# GRLV_double_30v_v0_2b.net
KiCad netlist of a schematic drawn in Altium Designer
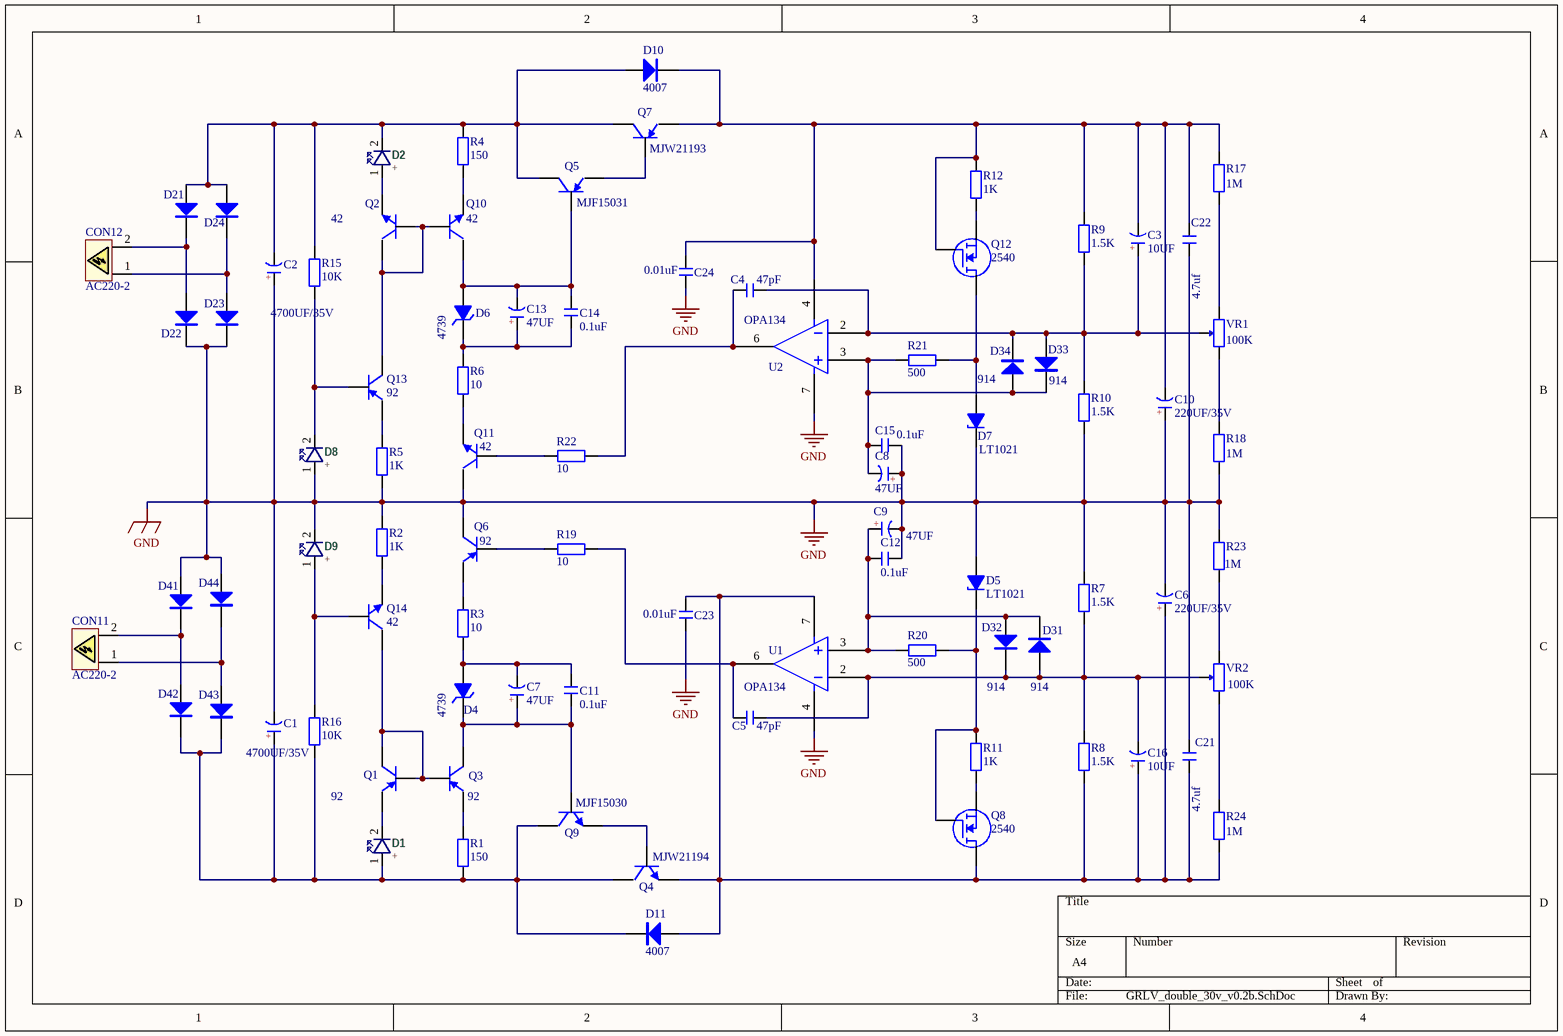
[diagram p0: GRLV_double_30v_v0.2b.SchDoc]

(export (version "E")
  (design (tool "Eeschema 10.0.6"))
  (components
    (comp (ref "C1")
      (value "4700UF/35V")
      (footprint "CAP 10*22*31.5")
      (description "直插电解电容")
      (fields (field (name "版权归属") "源创客"))
      (libsource (lib "电阻-电容-电感") (part "C-CAP"))
    )
    (comp (ref "C2")
      (value "4700UF/35V")
      (footprint "CAP 10*22*31.5")
      (description "直插电解电容")
      (fields (field (name "版权归属") "源创客"))
      (libsource (lib "电阻-电容-电感") (part "C-CAP"))
    )
    (comp (ref "C3")
      (value "10UF")
      (footprint "CAP 2.5*6.3*7")
      (description "直插电解电容")
      (fields (field (name "版权归属") "源创客"))
      (libsource (lib "电阻-电容-电感") (part "C-CAP"))
    )
    (comp (ref "C4")
      (value "47pF")
      (footprint "CBB 6.3*6.3*5")
      (description "CBB电容")
      (fields (field (name "版权归属") "源创客"))
      (libsource (lib "电阻-电容-电感") (part "C-CBB"))
    )
    (comp (ref "C5")
      (value "47pF")
      (footprint "CBB 6.3*6.3*5")
      (description "CBB电容")
      (fields (field (name "版权归属") "源创客"))
      (libsource (lib "电阻-电容-电感") (part "C-CBB"))
    )
    (comp (ref "C6")
      (value "220UF/35V")
      (footprint "CAP 3.5*8*11.5")
      (description "直插电解电容")
      (fields (field (name "版权归属") "源创客"))
      (libsource (lib "电阻-电容-电感") (part "C-CAP"))
    )
    (comp (ref "C7")
      (value "47UF")
      (footprint "CAP 2.5*6.3*11.2")
      (description "直插电解电容")
      (fields (field (name "版权归属") "源创客"))
      (libsource (lib "电阻-电容-电感") (part "C-CAP"))
    )
    (comp (ref "C8")
      (value "47UF")
      (footprint "CAP 2.5*6.3*11.2")
      (description "直插电解电容")
      (fields (field (name "版权归属") "源创客"))
      (libsource (lib "") (part "C-CAP_1"))
    )
    (comp (ref "C9")
      (value "47UF")
      (footprint "CAP 2.5*6.3*11.2")
      (description "直插电解电容")
      (fields (field (name "版权归属") "源创客"))
      (libsource (lib "") (part "C-CAP_1"))
    )
    (comp (ref "C10")
      (value "220UF/35V")
      (footprint "CAP 3.5*8*11.5")
      (description "直插电解电容")
      (fields (field (name "版权归属") "源创客"))
      (libsource (lib "电阻-电容-电感") (part "C-CAP"))
    )
    (comp (ref "C11")
      (value "0.1uF")
      (footprint "CBB 6.3*6.3*5")
      (description "CBB电容")
      (fields (field (name "版权归属") "源创客"))
      (libsource (lib "电阻-电容-电感") (part "C-CBB"))
    )
    (comp (ref "C12")
      (value "0.1uF")
      (footprint "CBB 6.3*6.3*5")
      (description "CBB电容")
      (fields (field (name "版权归属") "源创客"))
      (libsource (lib "电阻-电容-电感") (part "C-CBB"))
    )
    (comp (ref "C13")
      (value "47UF")
      (footprint "CAP 2.5*6.3*11.2")
      (description "直插电解电容")
      (fields (field (name "版权归属") "源创客"))
      (libsource (lib "电阻-电容-电感") (part "C-CAP"))
    )
    (comp (ref "C14")
      (value "0.1uF")
      (footprint "CBB 6.3*6.3*5")
      (description "CBB电容")
      (fields (field (name "版权归属") "源创客"))
      (libsource (lib "电阻-电容-电感") (part "C-CBB"))
    )
    (comp (ref "C15")
      (value "0.1uF")
      (footprint "CBB 6.3*6.3*5")
      (description "CBB电容")
      (fields (field (name "版权归属") "源创客"))
      (libsource (lib "电阻-电容-电感") (part "C-CBB"))
    )
    (comp (ref "C16")
      (value "10UF")
      (footprint "CAP 2.5*6.3*7")
      (description "直插电解电容")
      (fields (field (name "版权归属") "源创客"))
      (libsource (lib "电阻-电容-电感") (part "C-CAP"))
    )
    (comp (ref "C21")
      (value "4.7uf")
      (footprint "CBB 7.2*7.2*13")
      (description "MKS薄膜电容")
      (libsource (lib "电阻-电容-电感") (part "C-MKS"))
    )
    (comp (ref "C22")
      (value "4.7uf")
      (footprint "CBB 7.2*7.2*13")
      (description "MKS薄膜电容")
      (libsource (lib "电阻-电容-电感") (part "C-MKS"))
    )
    (comp (ref "C23")
      (value "0.01uF")
      (footprint "CBB 6.3*6.3*5")
      (description "CBB电容")
      (fields (field (name "Comment") ".01") (field (name "版权归属") "源创客"))
      (libsource (lib "电阻-电容-电感") (part "C-CBB"))
    )
    (comp (ref "C24")
      (value "0.01uF")
      (footprint "CBB 6.3*6.3*5")
      (description "CBB电容")
      (fields (field (name "Comment") ".01") (field (name "版权归属") "源创客"))
      (libsource (lib "电阻-电容-电感") (part "C-CBB"))
    )
    (comp (ref "CON11")
      (value "AC220-2")
      (footprint "HX4.0-2XS")
      (libsource (lib "Connectors") (part "AC220-2"))
    )
    (comp (ref "CON12")
      (value "AC220-2")
      (footprint "HX4.0-2XS")
      (libsource (lib "Connectors") (part "AC220-2"))
    )
    (comp (ref "D1")
      (value "+")
      (footprint "LED 3MM-R")
      (description "直插式LED")
      (libsource (lib "LED") (part "LED"))
    )
    (comp (ref "D2")
      (value "+")
      (footprint "LED 3MM-R")
      (description "直插式LED")
      (libsource (lib "LED") (part "LED"))
    )
    (comp (ref "D4")
      (value "4739")
      (footprint "DO-41")
      (description "9.1V/1W稳压管")
      (libsource (lib "二极管-整流桥") (part "1N4739"))
    )
    (comp (ref "D5")
      (value "LT1021")
      (footprint "DIP8-300_MH")
      (description "10V Precision Reference 2 Pin Config")
      (libsource (lib "电压参考") (part "LT1021-10-2P"))
    )
    (comp (ref "D6")
      (value "4739")
      (footprint "DO-41")
      (description "9.1V/1W稳压管")
      (libsource (lib "二极管-整流桥") (part "1N4739"))
    )
    (comp (ref "D7")
      (value "LT1021")
      (footprint "DIP8-300_MH")
      (description "10V Precision Reference 2 Pin Config")
      (libsource (lib "电压参考") (part "LT1021-10-2P"))
    )
    (comp (ref "D8")
      (value "+")
      (footprint "LED 3MM-R")
      (description "直插式LED")
      (libsource (lib "LED") (part "LED"))
    )
    (comp (ref "D9")
      (value "+")
      (footprint "LED 3MM-R")
      (description "直插式LED")
      (libsource (lib "LED") (part "LED"))
    )
    (comp (ref "D10")
      (value "4007")
      (footprint "DO-41")
      (description "整流二极管")
      (fields (field (name "版权归属") "源创客"))
      (libsource (lib "二极管-整流桥") (part "1N4007"))
    )
    (comp (ref "D11")
      (value "4007")
      (footprint "DO-41")
      (description "整流二极管")
      (fields (field (name "版权归属") "源创客"))
      (libsource (lib "二极管-整流桥") (part "1N4007"))
    )
    (comp (ref "D21")
      (value "HFA08")
      (footprint "TO220AC")
      (description "Ultrafast Soft Recovery Diado 8A 600V")
      (libsource (lib "二极管-整流桥") (part "VS-HFA08TB60-M3"))
    )
    (comp (ref "D22")
      (value "HFA08")
      (footprint "TO220AC")
      (description "Ultrafast Soft Recovery Diado 8A 600V")
      (libsource (lib "二极管-整流桥") (part "VS-HFA08TB60-M3"))
    )
    (comp (ref "D23")
      (value "HFA08")
      (footprint "TO220AC")
      (description "Ultrafast Soft Recovery Diado 8A 600V")
      (libsource (lib "二极管-整流桥") (part "VS-HFA08TB60-M3"))
    )
    (comp (ref "D24")
      (value "HFA08")
      (footprint "TO220AC")
      (description "Ultrafast Soft Recovery Diado 8A 600V")
      (libsource (lib "二极管-整流桥") (part "VS-HFA08TB60-M3"))
    )
    (comp (ref "D31")
      (value "914")
      (footprint "DO-35")
      (description "高速开关管 1V/0.25W")
      (libsource (lib "二极管-整流桥") (part "1N914"))
    )
    (comp (ref "D32")
      (value "914")
      (footprint "DO-35")
      (description "高速开关管 1V/0.25W")
      (libsource (lib "二极管-整流桥") (part "1N914"))
    )
    (comp (ref "D33")
      (value "914")
      (footprint "DO-35")
      (description "高速开关管 1V/0.25W")
      (libsource (lib "二极管-整流桥") (part "1N914"))
    )
    (comp (ref "D34")
      (value "914")
      (footprint "DO-35")
      (description "高速开关管 1V/0.25W")
      (libsource (lib "二极管-整流桥") (part "1N914"))
    )
    (comp (ref "D41")
      (value "VS-HFA08TB60-M3")
      (footprint "TO220AC")
      (description "Ultrafast Soft Recovery Diado 8A 600V")
      (libsource (lib "二极管-整流桥") (part "VS-HFA08TB60-M3"))
    )
    (comp (ref "D42")
      (value "VS-HFA08TB60-M3")
      (footprint "TO220AC")
      (description "Ultrafast Soft Recovery Diado 8A 600V")
      (libsource (lib "二极管-整流桥") (part "VS-HFA08TB60-M3"))
    )
    (comp (ref "D43")
      (value "VS-HFA08TB60-M3")
      (footprint "TO220AC")
      (description "Ultrafast Soft Recovery Diado 8A 600V")
      (libsource (lib "二极管-整流桥") (part "VS-HFA08TB60-M3"))
    )
    (comp (ref "D44")
      (value "VS-HFA08TB60-M3")
      (footprint "TO220AC")
      (description "Ultrafast Soft Recovery Diado 8A 600V")
      (libsource (lib "二极管-整流桥") (part "VS-HFA08TB60-M3"))
    )
    (comp (ref "Q1")
      (value "92")
      (footprint "TO92A")
      (description "High Voltage PNP Transistor")
      (libsource (lib "三极管") (part "KSP92/93"))
    )
    (comp (ref "Q2")
      (value "42")
      (footprint "TO92A")
      (description "High Voltage NPN Transistor")
      (libsource (lib "三极管") (part "KSP42/43"))
    )
    (comp (ref "Q3")
      (value "92")
      (footprint "TO92A")
      (description "High Voltage PNP Transistor")
      (libsource (lib "三极管") (part "KSP92/93"))
    )
    (comp (ref "Q4")
      (value "MJW21194")
      (footprint "TO247V")
      (description "Power NPN Transistor")
      (libsource (lib "三极管") (part "MJW21194"))
    )
    (comp (ref "Q5")
      (value "MJF15031")
      (footprint "TO220V")
      (description "Power PNP Transistor")
      (libsource (lib "三极管") (part "MJF15031"))
    )
    (comp (ref "Q6")
      (value "92")
      (footprint "TO92A")
      (description "High Voltage PNP Transistor")
      (libsource (lib "三极管") (part "KSP92/93"))
    )
    (comp (ref "Q7")
      (value "MJW21193")
      (footprint "TO247V")
      (description "Power PNP Transistor")
      (libsource (lib "三极管") (part "MJW21193"))
    )
    (comp (ref "Q8")
      (value "2540")
      (footprint "TO92A")
      (description "N沟道耗尽型DMOS场效应管 400V/150ma")
      (libsource (lib "场效应管") (part "DN2540"))
    )
    (comp (ref "Q9")
      (value "MJF15030")
      (footprint "TO220V")
      (description "Power NPN Transistor")
      (libsource (lib "三极管") (part "MJF15030"))
    )
    (comp (ref "Q10")
      (value "42")
      (footprint "TO92A")
      (description "High Voltage NPN Transistor")
      (libsource (lib "三极管") (part "KSP42/43"))
    )
    (comp (ref "Q11")
      (value "42")
      (footprint "TO92A")
      (description "High Voltage NPN Transistor")
      (libsource (lib "三极管") (part "KSP42/43"))
    )
    (comp (ref "Q12")
      (value "2540")
      (footprint "TO92A")
      (description "N沟道耗尽型DMOS场效应管 400V/150ma")
      (libsource (lib "场效应管") (part "DN2540"))
    )
    (comp (ref "Q13")
      (value "92")
      (footprint "TO92A")
      (description "High Voltage PNP Transistor")
      (libsource (lib "三极管") (part "KSP92/93"))
    )
    (comp (ref "Q14")
      (value "42")
      (footprint "TO92A")
      (description "High Voltage NPN Transistor")
      (libsource (lib "三极管") (part "KSP42/43"))
    )
    (comp (ref "R1")
      (value "150")
      (footprint "RS 1/4W")
      (description "直插色环电阻")
      (fields (field (name "版权归属") "源创客"))
      (libsource (lib "电阻-电容-电感") (part "R-CRR"))
    )
    (comp (ref "R2")
      (value "1K")
      (footprint "RS 1/4W")
      (description "直插色环电阻")
      (fields (field (name "版权归属") "源创客"))
      (libsource (lib "电阻-电容-电感") (part "R-CRR"))
    )
    (comp (ref "R3")
      (value "10")
      (footprint "RS 1/4W")
      (description "直插色环电阻")
      (fields (field (name "版权归属") "源创客"))
      (libsource (lib "电阻-电容-电感") (part "R-CRR"))
    )
    (comp (ref "R4")
      (value "150")
      (footprint "RS 1/4W")
      (description "直插色环电阻")
      (fields (field (name "版权归属") "源创客"))
      (libsource (lib "电阻-电容-电感") (part "R-CRR"))
    )
    (comp (ref "R5")
      (value "1K")
      (footprint "RS 1/4W")
      (description "直插色环电阻")
      (fields (field (name "版权归属") "源创客"))
      (libsource (lib "电阻-电容-电感") (part "R-CRR"))
    )
    (comp (ref "R6")
      (value "10")
      (footprint "RS 1/4W")
      (description "直插色环电阻")
      (fields (field (name "版权归属") "源创客"))
      (libsource (lib "电阻-电容-电感") (part "R-CRR"))
    )
    (comp (ref "R7")
      (value "1.5K")
      (footprint "RS 1/4W")
      (description "直插色环电阻")
      (fields (field (name "版权归属") "源创客"))
      (libsource (lib "电阻-电容-电感") (part "R-CRR"))
    )
    (comp (ref "R8")
      (value "1.5K")
      (footprint "RS 1/4W")
      (description "直插色环电阻")
      (fields (field (name "版权归属") "源创客"))
      (libsource (lib "电阻-电容-电感") (part "R-CRR"))
    )
    (comp (ref "R9")
      (value "1.5K")
      (footprint "RS 1/4W")
      (description "直插色环电阻")
      (fields (field (name "版权归属") "源创客"))
      (libsource (lib "电阻-电容-电感") (part "R-CRR"))
    )
    (comp (ref "R10")
      (value "1.5K")
      (footprint "RS 1/4W")
      (description "直插色环电阻")
      (fields (field (name "版权归属") "源创客"))
      (libsource (lib "电阻-电容-电感") (part "R-CRR"))
    )
    (comp (ref "R11")
      (value "1K")
      (footprint "RS 1/4W")
      (description "直插色环电阻")
      (fields (field (name "版权归属") "源创客"))
      (libsource (lib "电阻-电容-电感") (part "R-CRR"))
    )
    (comp (ref "R12")
      (value "1K")
      (footprint "RS 1/4W")
      (description "直插色环电阻")
      (fields (field (name "版权归属") "源创客"))
      (libsource (lib "电阻-电容-电感") (part "R-CRR"))
    )
    (comp (ref "R15")
      (value "10K")
      (footprint "RS 1/4W")
      (description "直插色环电阻")
      (fields (field (name "版权归属") "源创客"))
      (libsource (lib "电阻-电容-电感") (part "R-CRR"))
    )
    (comp (ref "R16")
      (value "10K")
      (footprint "RS 1/4W")
      (description "直插色环电阻")
      (fields (field (name "版权归属") "源创客"))
      (libsource (lib "电阻-电容-电感") (part "R-CRR"))
    )
    (comp (ref "R17")
      (value "1M")
      (footprint "RS 1/4W")
      (description "直插色环电阻")
      (fields (field (name "版权归属") "源创客"))
      (libsource (lib "电阻-电容-电感") (part "R-CRR"))
    )
    (comp (ref "R18")
      (value "1M")
      (footprint "RS 1/4W")
      (description "直插色环电阻")
      (fields (field (name "版权归属") "源创客"))
      (libsource (lib "电阻-电容-电感") (part "R-CRR"))
    )
    (comp (ref "R19")
      (value "10")
      (footprint "RS 1/4W")
      (description "直插色环电阻")
      (fields (field (name "版权归属") "源创客"))
      (libsource (lib "电阻-电容-电感") (part "R-CRR"))
    )
    (comp (ref "R20")
      (value "500")
      (footprint "RS 1/4W")
      (description "直插色环电阻")
      (fields (field (name "版权归属") "源创客"))
      (libsource (lib "电阻-电容-电感") (part "R-CRR"))
    )
    (comp (ref "R21")
      (value "500")
      (footprint "RS 1/4W")
      (description "直插色环电阻")
      (fields (field (name "版权归属") "源创客"))
      (libsource (lib "电阻-电容-电感") (part "R-CRR"))
    )
    (comp (ref "R22")
      (value "10")
      (footprint "RS 1/4W")
      (description "直插色环电阻")
      (fields (field (name "版权归属") "源创客"))
      (libsource (lib "电阻-电容-电感") (part "R-CRR"))
    )
    (comp (ref "R23")
      (value "1M")
      (footprint "RS 1/4W")
      (description "直插色环电阻")
      (fields (field (name "版权归属") "源创客"))
      (libsource (lib "电阻-电容-电感") (part "R-CRR"))
    )
    (comp (ref "R24")
      (value "1M")
      (footprint "RS 1/4W")
      (description "直插色环电阻")
      (fields (field (name "版权归属") "源创客"))
      (libsource (lib "电阻-电容-电感") (part "R-CRR"))
    )
    (comp (ref "U1") (value "OPA134") (footprint "DIP8-300_MH") (libsource (lib "运放") (part "OPA134PA")))
    (comp (ref "U2") (value "OPA134") (footprint "DIP8-300_MH") (libsource (lib "运放") (part "OPA134PA")))
    (comp (ref "VR1")
      (value "100K")
      (footprint "RS 1/2W-VR")
      (description "直插可调电阻-顶调")
      (libsource (lib "电阻-电容-电感") (part "VR-W"))
    )
    (comp (ref "VR2")
      (value "100K")
      (footprint "RS 1/2W-VR")
      (description "直插可调电阻-顶调")
      (libsource (lib "电阻-电容-电感") (part "VR-W"))
    )
  )
  (nets
    (net (code "1") (name "GND") (class "Default")
      (node (ref "C1") (pin "2") (pinfunction "K_2") (pintype "passive"))
      (node (ref "C10") (pin "1") (pinfunction "A_1") (pintype "passive"))
      (node (ref "C12") (pin "2") (pinfunction "2_2") (pintype "passive"))
      (node (ref "C15") (pin "2") (pinfunction "2_2") (pintype "passive"))
      (node (ref "C2") (pin "1") (pinfunction "A_1") (pintype "passive"))
      (node (ref "C21") (pin "2") (pinfunction "2_2") (pintype "passive"))
      (node (ref "C22") (pin "1") (pinfunction "1_1") (pintype "passive"))
      (node (ref "C23") (pin "1") (pinfunction "1_1") (pintype "passive"))
      (node (ref "C24") (pin "1") (pinfunction "1_1") (pintype "passive"))
      (node (ref "C6") (pin "2") (pinfunction "K_2") (pintype "passive"))
      (node (ref "C8") (pin "1") (pinfunction "A_1") (pintype "passive"))
      (node (ref "C9") (pin "2") (pinfunction "K_2") (pintype "passive"))
      (node (ref "D22") (pin "1") (pinfunction "Cathode_1") (pintype "passive"))
      (node (ref "D23") (pin "1") (pinfunction "Cathode_1") (pintype "passive"))
      (node (ref "D41") (pin "2") (pinfunction "Anode_2") (pintype "passive"))
      (node (ref "D44") (pin "2") (pinfunction "Anode_2") (pintype "passive"))
      (node (ref "D5") (pin "4") (pinfunction "A_4") (pintype "passive"))
      (node (ref "D7") (pin "6") (pinfunction "K_6") (pintype "passive"))
      (node (ref "D8") (pin "1") (pinfunction "A_1") (pintype "passive"))
      (node (ref "D9") (pin "2") (pinfunction "K_2") (pintype "passive"))
      (node (ref "Q11") (pin "3") (pinfunction "C_3") (pintype "passive"))
      (node (ref "Q6") (pin "3") (pinfunction "C_3") (pintype "passive"))
      (node (ref "R10") (pin "1") (pinfunction "1_1") (pintype "passive"))
      (node (ref "R18") (pin "1") (pinfunction "1_1") (pintype "passive"))
      (node (ref "R2") (pin "2") (pinfunction "2_2") (pintype "passive"))
      (node (ref "R23") (pin "2") (pinfunction "2_2") (pintype "passive"))
      (node (ref "R5") (pin "1") (pinfunction "1_1") (pintype "passive"))
      (node (ref "R7") (pin "2") (pinfunction "2_2") (pintype "passive"))
      (node (ref "U1") (pin "4") (pinfunction "V-_4") (pintype "passive"))
      (node (ref "U2") (pin "7") (pinfunction "V+_7") (pintype "passive"))
    )
    (net (code "2") (name "Net-(C1-A)") (class "Default")
      (node (ref "C1") (pin "1") (pinfunction "A_1") (pintype "passive"))
      (node (ref "D1") (pin "1") (pinfunction "A_1") (pintype "passive"))
      (node (ref "D11") (pin "2") (pinfunction "K_2") (pintype "passive"))
      (node (ref "D42") (pin "1") (pinfunction "Cathode_1") (pintype "passive"))
      (node (ref "D43") (pin "1") (pinfunction "Cathode_1") (pintype "passive"))
      (node (ref "Q4") (pin "2") (pinfunction "C_2") (pintype "passive"))
      (node (ref "Q9") (pin "2") (pinfunction "C_2") (pintype "passive"))
      (node (ref "R1") (pin "1") (pinfunction "1_1") (pintype "passive"))
      (node (ref "R16") (pin "1") (pinfunction "1_1") (pintype "passive"))
    )
    (net (code "3") (name "Net-(C2-K)") (class "Default")
      (node (ref "C2") (pin "2") (pinfunction "K_2") (pintype "passive"))
      (node (ref "D10") (pin "1") (pinfunction "A_1") (pintype "passive"))
      (node (ref "D2") (pin "2") (pinfunction "K_2") (pintype "passive"))
      (node (ref "D21") (pin "2") (pinfunction "Anode_2") (pintype "passive"))
      (node (ref "D24") (pin "2") (pinfunction "Anode_2") (pintype "passive"))
      (node (ref "Q5") (pin "2") (pinfunction "C_2") (pintype "passive"))
      (node (ref "Q7") (pin "2") (pinfunction "C_2") (pintype "passive"))
      (node (ref "R15") (pin "2") (pinfunction "2_2") (pintype "passive"))
      (node (ref "R4") (pin "2") (pinfunction "2_2") (pintype "passive"))
    )
    (net (code "4") (name "Net-(C3-A)") (class "Default")
      (node (ref "C3") (pin "1") (pinfunction "A_1") (pintype "passive"))
      (node (ref "C4") (pin "2") (pinfunction "2_2") (pintype "passive"))
      (node (ref "D33") (pin "1") (pinfunction "A_1") (pintype "passive"))
      (node (ref "D34") (pin "2") (pinfunction "K_2") (pintype "passive"))
      (node (ref "R10") (pin "2") (pinfunction "2_2") (pintype "passive"))
      (node (ref "R9") (pin "1") (pinfunction "1_1") (pintype "passive"))
      (node (ref "U2") (pin "2") (pinfunction "-in_2") (pintype "passive"))
      (node (ref "VR1") (pin "3") (pinfunction "3_3") (pintype "passive"))
    )
    (net (code "5") (name "Net-(C7-A)") (class "Default")
      (node (ref "C11") (pin "1") (pinfunction "1_1") (pintype "passive"))
      (node (ref "C7") (pin "1") (pinfunction "A_1") (pintype "passive"))
      (node (ref "D4") (pin "2") (pinfunction "K_2") (pintype "passive"))
      (node (ref "Q3") (pin "3") (pinfunction "C_3") (pintype "passive"))
      (node (ref "Q9") (pin "1") (pinfunction "B_1") (pintype "passive"))
    )
    (net (code "6") (name "Net-(C7-K)") (class "Default")
      (node (ref "C11") (pin "2") (pinfunction "2_2") (pintype "passive"))
      (node (ref "C7") (pin "2") (pinfunction "K_2") (pintype "passive"))
      (node (ref "D4") (pin "1") (pinfunction "A_1") (pintype "passive"))
      (node (ref "R3") (pin "1") (pinfunction "1_1") (pintype "passive"))
    )
    (net (code "7") (name "Net-(C8-K)") (class "Default")
      (node (ref "C15") (pin "1") (pinfunction "1_1") (pintype "passive"))
      (node (ref "C8") (pin "2") (pinfunction "K_2") (pintype "passive"))
      (node (ref "D33") (pin "2") (pinfunction "K_2") (pintype "passive"))
      (node (ref "D34") (pin "1") (pinfunction "A_1") (pintype "passive"))
      (node (ref "R21") (pin "1") (pinfunction "1_1") (pintype "passive"))
      (node (ref "U2") (pin "3") (pinfunction "+in_3") (pintype "passive"))
    )
    (net (code "8") (name "Net-(C9-A)") (class "Default")
      (node (ref "C12") (pin "1") (pinfunction "1_1") (pintype "passive"))
      (node (ref "C9") (pin "1") (pinfunction "A_1") (pintype "passive"))
      (node (ref "D31") (pin "2") (pinfunction "K_2") (pintype "passive"))
      (node (ref "D32") (pin "1") (pinfunction "A_1") (pintype "passive"))
      (node (ref "R20") (pin "1") (pinfunction "1_1") (pintype "passive"))
      (node (ref "U1") (pin "3") (pinfunction "+in_3") (pintype "passive"))
    )
    (net (code "9") (name "Net-(C10-K)") (class "Default")
      (node (ref "C10") (pin "2") (pinfunction "K_2") (pintype "passive"))
      (node (ref "C22") (pin "2") (pinfunction "2_2") (pintype "passive"))
      (node (ref "C24") (pin "2") (pinfunction "2_2") (pintype "passive"))
      (node (ref "C3") (pin "2") (pinfunction "K_2") (pintype "passive"))
      (node (ref "D10") (pin "2") (pinfunction "K_2") (pintype "passive"))
      (node (ref "Q12") (pin "2") (pinfunction "G_2") (pintype "passive"))
      (node (ref "Q7") (pin "3") (pinfunction "E_3") (pintype "passive"))
      (node (ref "R12") (pin "2") (pinfunction "2_2") (pintype "passive"))
      (node (ref "R17") (pin "2") (pinfunction "2_2") (pintype "passive"))
      (node (ref "R9") (pin "2") (pinfunction "2_2") (pintype "passive"))
      (node (ref "U2") (pin "4") (pinfunction "V-_4") (pintype "passive"))
    )
    (net (code "10") (name "Net-(C13-A)") (class "Default")
      (node (ref "C13") (pin "1") (pinfunction "A_1") (pintype "passive"))
      (node (ref "C14") (pin "1") (pinfunction "1_1") (pintype "passive"))
      (node (ref "D6") (pin "2") (pinfunction "K_2") (pintype "passive"))
      (node (ref "R6") (pin "2") (pinfunction "2_2") (pintype "passive"))
    )
    (net (code "11") (name "Net-(C13-K)") (class "Default")
      (node (ref "C13") (pin "2") (pinfunction "K_2") (pintype "passive"))
      (node (ref "C14") (pin "2") (pinfunction "2_2") (pintype "passive"))
      (node (ref "D6") (pin "1") (pinfunction "A_1") (pintype "passive"))
      (node (ref "Q10") (pin "3") (pinfunction "C_3") (pintype "passive"))
      (node (ref "Q5") (pin "1") (pinfunction "B_1") (pintype "passive"))
    )
    (net (code "12") (name "Net-(C16-A)") (class "Default")
      (node (ref "C16") (pin "1") (pinfunction "A_1") (pintype "passive"))
      (node (ref "C21") (pin "1") (pinfunction "1_1") (pintype "passive"))
      (node (ref "C23") (pin "2") (pinfunction "2_2") (pintype "passive"))
      (node (ref "C6") (pin "1") (pinfunction "A_1") (pintype "passive"))
      (node (ref "D11") (pin "1") (pinfunction "A_1") (pintype "passive"))
      (node (ref "Q4") (pin "3") (pinfunction "E_3") (pintype "passive"))
      (node (ref "Q8") (pin "3") (pinfunction "D_3") (pintype "passive"))
      (node (ref "R24") (pin "1") (pinfunction "1_1") (pintype "passive"))
      (node (ref "R8") (pin "1") (pinfunction "1_1") (pintype "passive"))
      (node (ref "U1") (pin "7") (pinfunction "V+_7") (pintype "passive"))
    )
    (net (code "13") (name "Net-(C16-K)") (class "Default")
      (node (ref "C16") (pin "2") (pinfunction "K_2") (pintype "passive"))
      (node (ref "C5") (pin "2") (pinfunction "2_2") (pintype "passive"))
      (node (ref "D31") (pin "1") (pinfunction "A_1") (pintype "passive"))
      (node (ref "D32") (pin "2") (pinfunction "K_2") (pintype "passive"))
      (node (ref "R7") (pin "1") (pinfunction "1_1") (pintype "passive"))
      (node (ref "R8") (pin "2") (pinfunction "2_2") (pintype "passive"))
      (node (ref "U1") (pin "2") (pinfunction "-in_2") (pintype "passive"))
      (node (ref "VR2") (pin "3") (pinfunction "3_3") (pintype "passive"))
    )
    (net (code "14") (name "Net-(CON11-G)") (class "Default")
      (node (ref "CON11") (pin "2") (pinfunction "G_2") (pintype "passive"))
      (node (ref "D41") (pin "1") (pinfunction "Cathode_1") (pintype "passive"))
      (node (ref "D42") (pin "2") (pinfunction "Anode_2") (pintype "passive"))
    )
    (net (code "15") (name "Net-(CON11-L)") (class "Default")
      (node (ref "CON11") (pin "1") (pinfunction "L_1") (pintype "passive"))
      (node (ref "D43") (pin "2") (pinfunction "Anode_2") (pintype "passive"))
      (node (ref "D44") (pin "1") (pinfunction "Cathode_1") (pintype "passive"))
    )
    (net (code "16") (name "Net-(CON12-G)") (class "Default")
      (node (ref "CON12") (pin "2") (pinfunction "G_2") (pintype "passive"))
      (node (ref "D21") (pin "1") (pinfunction "Cathode_1") (pintype "passive"))
      (node (ref "D22") (pin "2") (pinfunction "Anode_2") (pintype "passive"))
    )
    (net (code "17") (name "Net-(CON12-L)") (class "Default")
      (node (ref "CON12") (pin "1") (pinfunction "L_1") (pintype "passive"))
      (node (ref "D23") (pin "2") (pinfunction "Anode_2") (pintype "passive"))
      (node (ref "D24") (pin "1") (pinfunction "Cathode_1") (pintype "passive"))
    )
    (net (code "18") (name "Net-(D1-K)") (class "Default")
      (node (ref "D1") (pin "2") (pinfunction "K_2") (pintype "passive"))
      (node (ref "Q1") (pin "1") (pinfunction "E_1") (pintype "passive"))
    )
    (net (code "19") (name "Net-(D2-A)") (class "Default")
      (node (ref "D2") (pin "1") (pinfunction "A_1") (pintype "passive"))
      (node (ref "Q2") (pin "1") (pinfunction "E_1") (pintype "passive"))
    )
    (net (code "20") (name "Net-(D5-K)") (class "Default")
      (node (ref "D5") (pin "6") (pinfunction "K_6") (pintype "passive"))
      (node (ref "Q8") (pin "2") (pinfunction "G_2") (pintype "passive"))
      (node (ref "R11") (pin "2") (pinfunction "2_2") (pintype "passive"))
      (node (ref "R20") (pin "2") (pinfunction "2_2") (pintype "passive"))
    )
    (net (code "21") (name "Net-(D7-A)") (class "Default")
      (node (ref "D7") (pin "4") (pinfunction "A_4") (pintype "passive"))
      (node (ref "Q12") (pin "3") (pinfunction "D_3") (pintype "passive"))
      (node (ref "R21") (pin "2") (pinfunction "2_2") (pintype "passive"))
    )
    (net (code "22") (name "Net-(D8-K)") (class "Default")
      (node (ref "D8") (pin "2") (pinfunction "K_2") (pintype "passive"))
      (node (ref "Q13") (pin "2") (pinfunction "B_2") (pintype "passive"))
      (node (ref "R15") (pin "1") (pinfunction "1_1") (pintype "passive"))
    )
    (net (code "23") (name "Net-(D9-A)") (class "Default")
      (node (ref "D9") (pin "1") (pinfunction "A_1") (pintype "passive"))
      (node (ref "Q14") (pin "2") (pinfunction "B_2") (pintype "passive"))
      (node (ref "R16") (pin "2") (pinfunction "2_2") (pintype "passive"))
    )
    (net (code "24") (name "Net-(Q1-B)") (class "Default")
      (node (ref "Q1") (pin "2") (pinfunction "B_2") (pintype "passive"))
      (node (ref "Q1") (pin "3") (pinfunction "C_3") (pintype "passive"))
      (node (ref "Q14") (pin "3") (pinfunction "C_3") (pintype "passive"))
      (node (ref "Q3") (pin "2") (pinfunction "B_2") (pintype "passive"))
    )
    (net (code "25") (name "Net-(Q3-E)") (class "Default")
      (node (ref "Q3") (pin "1") (pinfunction "E_1") (pintype "passive"))
      (node (ref "R1") (pin "2") (pinfunction "2_2") (pintype "passive"))
    )
    (net (code "26") (name "Net-(Q4-B)") (class "Default")
      (node (ref "Q4") (pin "1") (pinfunction "B_1") (pintype "passive"))
      (node (ref "Q9") (pin "3") (pinfunction "E_3") (pintype "passive"))
    )
    (net (code "27") (name "Net-(Q5-E)") (class "Default")
      (node (ref "Q5") (pin "3") (pinfunction "E_3") (pintype "passive"))
      (node (ref "Q7") (pin "1") (pinfunction "B_1") (pintype "passive"))
    )
    (net (code "28") (name "Net-(Q6-B)") (class "Default")
      (node (ref "Q6") (pin "2") (pinfunction "B_2") (pintype "passive"))
      (node (ref "R19") (pin "1") (pinfunction "1_1") (pintype "passive"))
    )
    (net (code "29") (name "Net-(Q6-E)") (class "Default")
      (node (ref "Q6") (pin "1") (pinfunction "E_1") (pintype "passive"))
      (node (ref "R3") (pin "2") (pinfunction "2_2") (pintype "passive"))
    )
    (net (code "30") (name "Net-(Q8-S)") (class "Default")
      (node (ref "Q8") (pin "1") (pinfunction "S_1") (pintype "passive"))
      (node (ref "R11") (pin "1") (pinfunction "1_1") (pintype "passive"))
    )
    (net (code "31") (name "Net-(Q10-B)") (class "Default")
      (node (ref "Q10") (pin "2") (pinfunction "B_2") (pintype "passive"))
      (node (ref "Q13") (pin "3") (pinfunction "C_3") (pintype "passive"))
      (node (ref "Q2") (pin "2") (pinfunction "B_2") (pintype "passive"))
      (node (ref "Q2") (pin "3") (pinfunction "C_3") (pintype "passive"))
    )
    (net (code "32") (name "Net-(Q10-E)") (class "Default")
      (node (ref "Q10") (pin "1") (pinfunction "E_1") (pintype "passive"))
      (node (ref "R4") (pin "1") (pinfunction "1_1") (pintype "passive"))
    )
    (net (code "33") (name "Net-(Q11-B)") (class "Default")
      (node (ref "Q11") (pin "2") (pinfunction "B_2") (pintype "passive"))
      (node (ref "R22") (pin "1") (pinfunction "1_1") (pintype "passive"))
    )
    (net (code "34") (name "Net-(Q11-E)") (class "Default")
      (node (ref "Q11") (pin "1") (pinfunction "E_1") (pintype "passive"))
      (node (ref "R6") (pin "1") (pinfunction "1_1") (pintype "passive"))
    )
    (net (code "35") (name "Net-(Q12-S)") (class "Default")
      (node (ref "Q12") (pin "1") (pinfunction "S_1") (pintype "passive"))
      (node (ref "R12") (pin "1") (pinfunction "1_1") (pintype "passive"))
    )
    (net (code "36") (name "Net-(Q13-E)") (class "Default")
      (node (ref "Q13") (pin "1") (pinfunction "E_1") (pintype "passive"))
      (node (ref "R5") (pin "2") (pinfunction "2_2") (pintype "passive"))
    )
    (net (code "37") (name "Net-(Q14-E)") (class "Default")
      (node (ref "Q14") (pin "1") (pinfunction "E_1") (pintype "passive"))
      (node (ref "R2") (pin "1") (pinfunction "1_1") (pintype "passive"))
    )
    (net (code "38") (name "Net-(R17-Pad1)") (class "Default")
      (node (ref "R17") (pin "1") (pinfunction "1_1") (pintype "passive"))
      (node (ref "VR1") (pin "2") (pinfunction "2_2") (pintype "passive"))
    )
    (net (code "39") (name "Net-(R18-Pad2)") (class "Default")
      (node (ref "R18") (pin "2") (pinfunction "2_2") (pintype "passive"))
      (node (ref "VR1") (pin "1") (pinfunction "1_1") (pintype "passive"))
    )
    (net (code "40") (name "Net-(R23-Pad1)") (class "Default")
      (node (ref "R23") (pin "1") (pinfunction "1_1") (pintype "passive"))
      (node (ref "VR2") (pin "2") (pinfunction "2_2") (pintype "passive"))
    )
    (net (code "41") (name "Net-(R24-Pad2)") (class "Default")
      (node (ref "R24") (pin "2") (pinfunction "2_2") (pintype "passive"))
      (node (ref "VR2") (pin "1") (pinfunction "1_1") (pintype "passive"))
    )
    (net (code "42") (name "Net-(U1-out)") (class "Default")
      (node (ref "C5") (pin "1") (pinfunction "1_1") (pintype "passive"))
      (node (ref "R19") (pin "2") (pinfunction "2_2") (pintype "passive"))
      (node (ref "U1") (pin "6") (pinfunction "out_6") (pintype "passive"))
    )
    (net (code "43") (name "Net-(U2-out)") (class "Default")
      (node (ref "C4") (pin "1") (pinfunction "1_1") (pintype "passive"))
      (node (ref "R22") (pin "2") (pinfunction "2_2") (pintype "passive"))
      (node (ref "U2") (pin "6") (pinfunction "out_6") (pintype "passive"))
    )
  )
)
